# MainConnector.net
KiCad netlist of a schematic drawn in Altium Designer
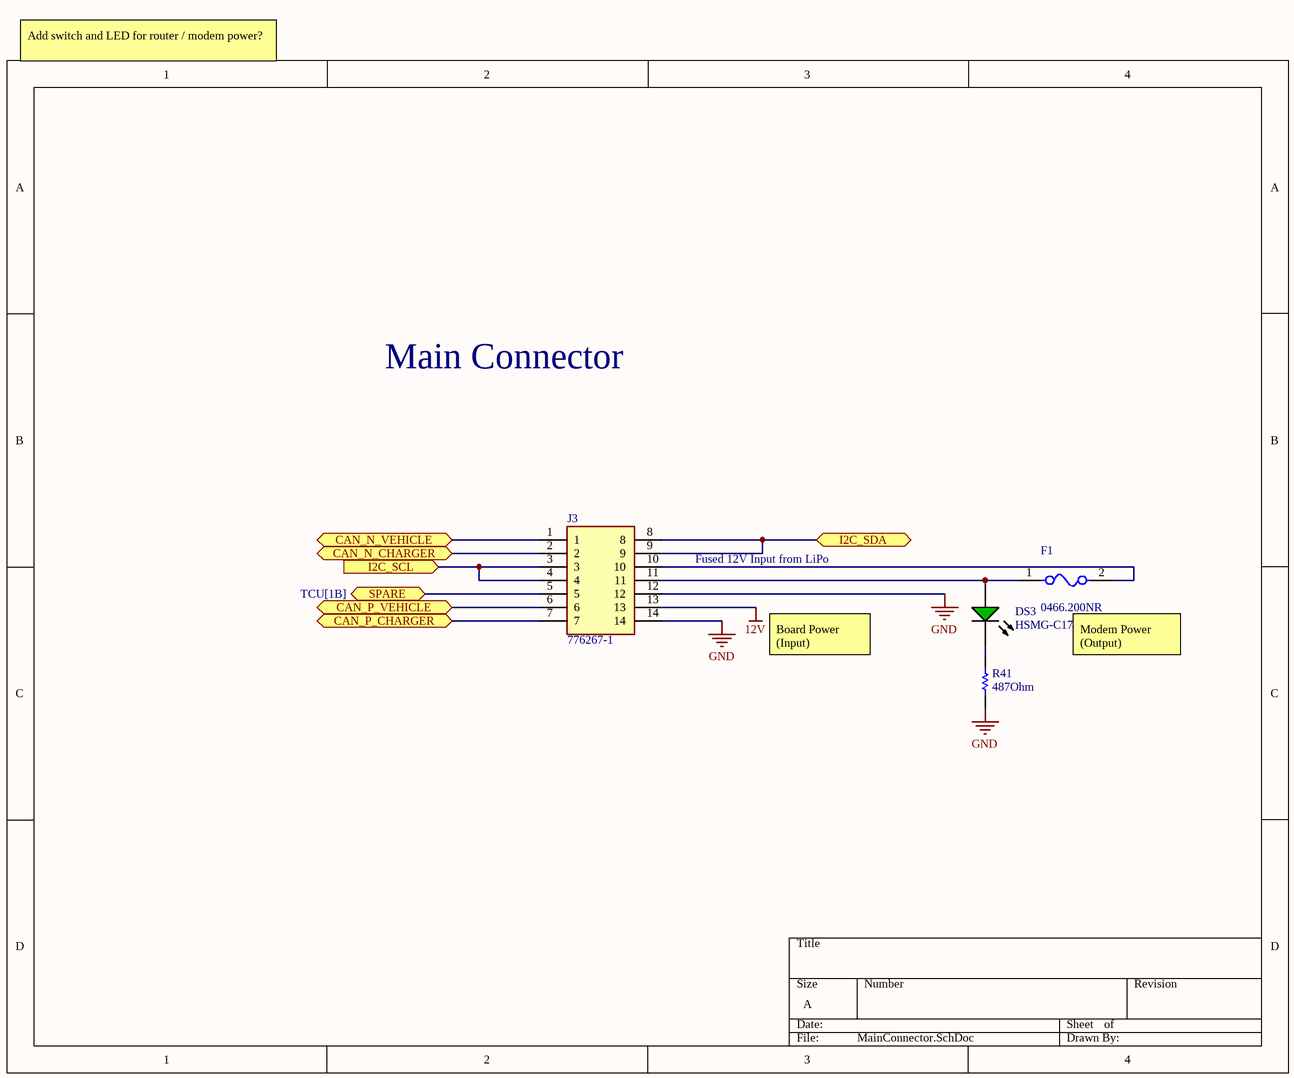
[diagram p0: MainConnector.SchDoc]

(export (version "E")
  (design (tool "Eeschema 10.0.6"))
  (components
    (comp (ref "DS3")
      (value "HSMG-C170")
      (footprint "AVAG-HSMX-C170_V")
      (description "Chip LED, Green, 2.2 V, -40 to 85 degC, 2-Pin SMD, Pb-Free, Tape and Reel")
      (fields (field (name "MANUFACTURER") "Avago"))
      (libsource (lib "Altium Content Vault") (part "LED_GREEN_A1K2-2"))
    )
    (comp (ref "F1")
      (value "0466.200NR")
      (footprint "FP-0466-MFG")
      (description "FUSE BOARD MNT 200MA 125VAC/VDC")
      (libsource (lib "Altium Content Vault") (part "5bcf9b9f640e542cf0359d10258e979"))
    )
    (comp (ref "J3")
      (value "776267-1")
      (footprint "SamacSys:776267-1")
      (description "Connector")
      (fields (field (name "MOUSER PART NUMBER") "571-776267-1"))
      (libsource (lib "*") (part "776267-1"))
    )
    (comp (ref "R41")
      (value "487Ohm")
      (footprint "RESC2013X60X35NL10T20")
      (fields (field (name "MANUFACTURER") "Yageo") (field (name "PART NUMBER") "RC0805FR-07487RL"))
      (libsource (lib "Altium Content Vault") (part "RES"))
    )
  )
  (nets
    (net (code "1") (name "/CAN_N_CHARGER") (class "Default")
      (node (ref "J3") (pin "2") (pinfunction "2_2") (pintype "passive"))
    )
    (net (code "2") (name "/CAN_N_VEHICLE") (class "Default")
      (node (ref "J3") (pin "1") (pinfunction "1_1") (pintype "passive"))
    )
    (net (code "3") (name "/CAN_P_CHARGER") (class "Default")
      (node (ref "J3") (pin "7") (pinfunction "7_7") (pintype "passive"))
    )
    (net (code "4") (name "/CAN_P_VEHICLE") (class "Default")
      (node (ref "J3") (pin "6") (pinfunction "6_6") (pintype "passive"))
    )
    (net (code "5") (name "/I2C_SCL") (class "Default")
      (node (ref "J3") (pin "3") (pinfunction "3_3") (pintype "passive"))
      (node (ref "J3") (pin "4") (pinfunction "4_4") (pintype "passive"))
    )
    (net (code "6") (name "/I2C_SDA") (class "Default")
      (node (ref "J3") (pin "8") (pinfunction "8_8") (pintype "passive"))
      (node (ref "J3") (pin "9") (pinfunction "9_9") (pintype "passive"))
    )
    (net (code "7") (name "/SPARE") (class "Default")
      (node (ref "J3") (pin "5") (pinfunction "5_5") (pintype "passive"))
    )
    (net (code "8") (name "12V") (class "Default")
      (node (ref "J3") (pin "13") (pinfunction "13_13") (pintype "passive"))
    )
    (net (code "9") (name "GND") (class "Default")
      (node (ref "J3") (pin "12") (pinfunction "12_12") (pintype "passive"))
      (node (ref "J3") (pin "14") (pinfunction "14_14") (pintype "passive"))
      (node (ref "R41") (pin "1") (pinfunction "1_1") (pintype "passive"))
    )
    (net (code "10") (name "Net-(DS3-A)") (class "Default")
      (node (ref "DS3") (pin "1") (pinfunction "A_1") (pintype "passive"))
      (node (ref "F1") (pin "1") (pinfunction "1_1") (pintype "passive"))
      (node (ref "J3") (pin "11") (pinfunction "11_11") (pintype "passive"))
    )
    (net (code "11") (name "Net-(DS3-K)") (class "Default")
      (node (ref "DS3") (pin "2") (pinfunction "K_2") (pintype "passive"))
      (node (ref "R41") (pin "2") (pinfunction "2_2") (pintype "passive"))
    )
    (net (code "12") (name "Net-(F1-Pad2)") (class "Default")
      (node (ref "F1") (pin "2") (pinfunction "2_2") (pintype "passive"))
      (node (ref "J3") (pin "10") (pinfunction "10_10") (pintype "passive"))
    )
  )
)
